# Sh_Outputs_Analog.net
KiCad netlist of a schematic drawn in Altium Designer
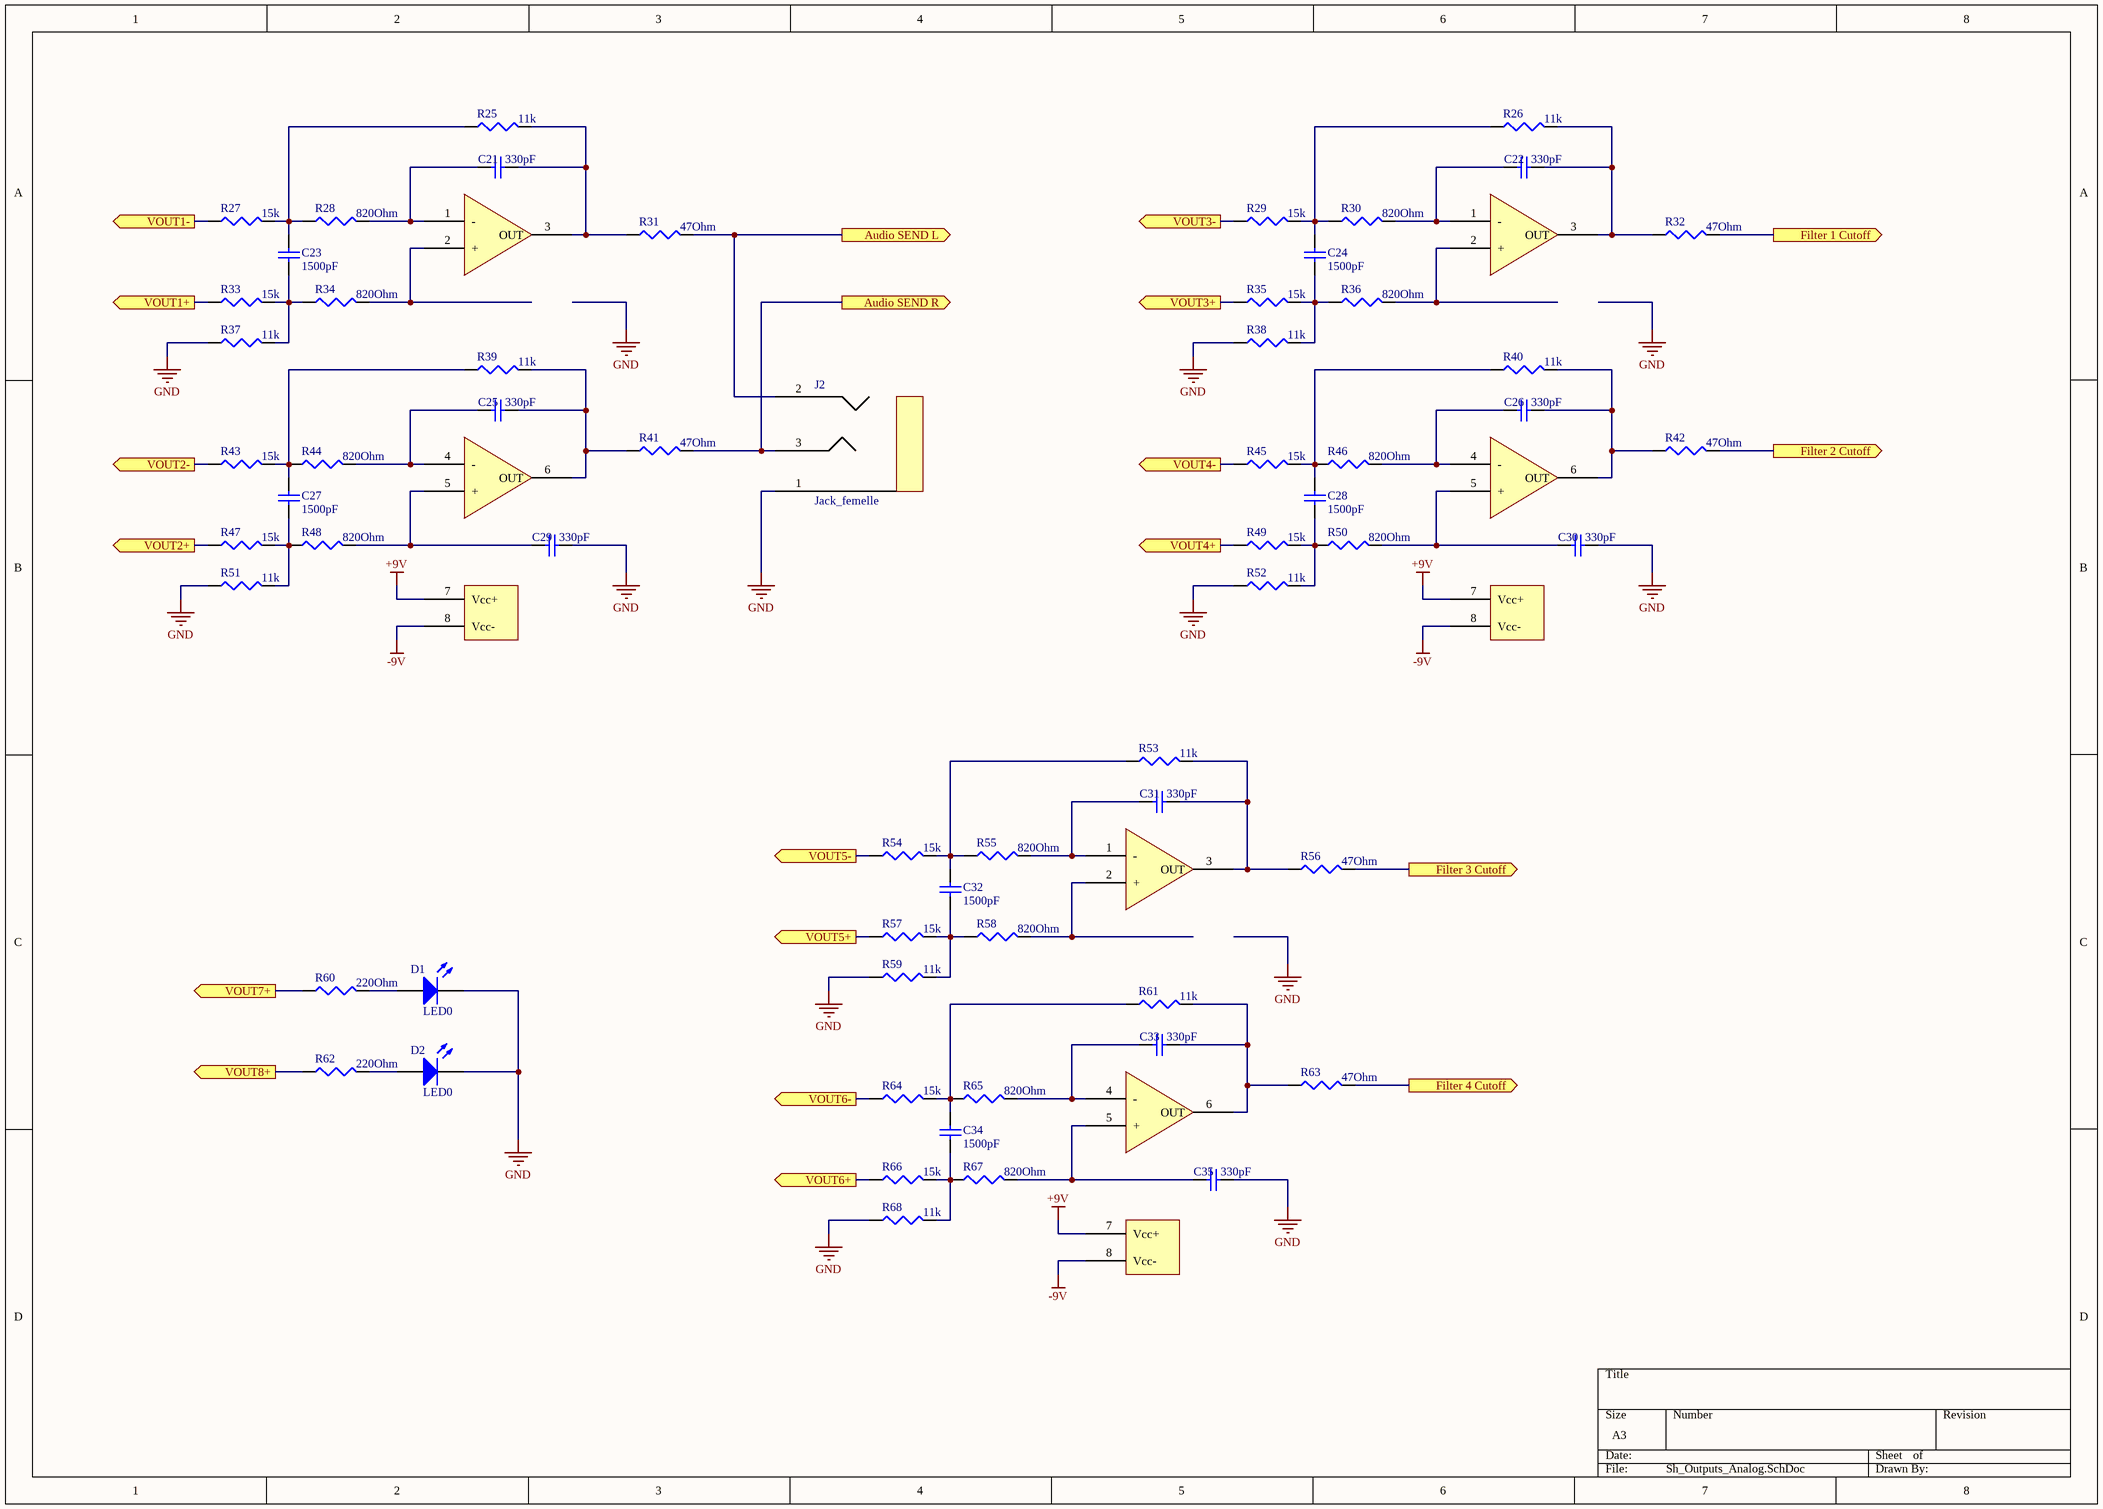
[diagram p0: Sh_Outputs_Analog.SchDoc]

(export (version "E")
  (design (tool "Eeschema 10.0.6"))
  (components
    (comp (ref "C21")
      (value "330pF")
      (footprint "1608[0603]")
      (description "Capacitor (Semiconductor SIM Model)")
      (fields (field (name "Comment") "Cap Semi") (field (name "PUBLISHER") "Altium Limited"))
      (libsource (lib "Miscellaneous Devices") (part "Cap Semi"))
    )
    (comp (ref "C22")
      (value "330pF")
      (footprint "1608[0603]")
      (description "Capacitor (Semiconductor SIM Model)")
      (fields (field (name "Comment") "Cap Semi") (field (name "PUBLISHER") "Altium Limited"))
      (libsource (lib "Miscellaneous Devices") (part "Cap Semi"))
    )
    (comp (ref "C23")
      (value "1500pF")
      (footprint "1608[0603]")
      (description "Capacitor (Semiconductor SIM Model)")
      (fields (field (name "Comment") "Cap Semi") (field (name "PUBLISHER") "Altium Limited"))
      (libsource (lib "Miscellaneous Devices") (part "Cap Semi"))
    )
    (comp (ref "C24")
      (value "1500pF")
      (footprint "1608[0603]")
      (description "Capacitor (Semiconductor SIM Model)")
      (fields (field (name "Comment") "Cap Semi") (field (name "PUBLISHER") "Altium Limited"))
      (libsource (lib "Miscellaneous Devices") (part "Cap Semi"))
    )
    (comp (ref "C25")
      (value "330pF")
      (footprint "1608[0603]")
      (description "Capacitor (Semiconductor SIM Model)")
      (fields (field (name "Comment") "Cap Semi") (field (name "PUBLISHER") "Altium Limited"))
      (libsource (lib "Miscellaneous Devices") (part "Cap Semi"))
    )
    (comp (ref "C26")
      (value "330pF")
      (footprint "1608[0603]")
      (description "Capacitor (Semiconductor SIM Model)")
      (fields (field (name "Comment") "Cap Semi") (field (name "PUBLISHER") "Altium Limited"))
      (libsource (lib "Miscellaneous Devices") (part "Cap Semi"))
    )
    (comp (ref "C27")
      (value "1500pF")
      (footprint "1608[0603]")
      (description "Capacitor (Semiconductor SIM Model)")
      (fields (field (name "Comment") "Cap Semi") (field (name "PUBLISHER") "Altium Limited"))
      (libsource (lib "Miscellaneous Devices") (part "Cap Semi"))
    )
    (comp (ref "C28")
      (value "1500pF")
      (footprint "1608[0603]")
      (description "Capacitor (Semiconductor SIM Model)")
      (fields (field (name "Comment") "Cap Semi") (field (name "PUBLISHER") "Altium Limited"))
      (libsource (lib "Miscellaneous Devices") (part "Cap Semi"))
    )
    (comp (ref "C29")
      (value "330pF")
      (footprint "1608[0603]")
      (description "Capacitor (Semiconductor SIM Model)")
      (fields (field (name "Comment") "Cap Semi") (field (name "PUBLISHER") "Altium Limited"))
      (libsource (lib "Miscellaneous Devices") (part "Cap Semi"))
    )
    (comp (ref "C30")
      (value "330pF")
      (footprint "1608[0603]")
      (description "Capacitor (Semiconductor SIM Model)")
      (fields (field (name "Comment") "Cap Semi") (field (name "PUBLISHER") "Altium Limited"))
      (libsource (lib "Miscellaneous Devices") (part "Cap Semi"))
    )
    (comp (ref "C31")
      (value "330pF")
      (footprint "1608[0603]")
      (description "Capacitor (Semiconductor SIM Model)")
      (fields (field (name "Comment") "Cap Semi") (field (name "PUBLISHER") "Altium Limited"))
      (libsource (lib "Miscellaneous Devices") (part "Cap Semi"))
    )
    (comp (ref "C32")
      (value "1500pF")
      (footprint "1608[0603]")
      (description "Capacitor (Semiconductor SIM Model)")
      (fields (field (name "Comment") "Cap Semi") (field (name "PUBLISHER") "Altium Limited"))
      (libsource (lib "Miscellaneous Devices") (part "Cap Semi"))
    )
    (comp (ref "C33")
      (value "330pF")
      (footprint "1608[0603]")
      (description "Capacitor (Semiconductor SIM Model)")
      (fields (field (name "Comment") "Cap Semi") (field (name "PUBLISHER") "Altium Limited"))
      (libsource (lib "Miscellaneous Devices") (part "Cap Semi"))
    )
    (comp (ref "C34")
      (value "1500pF")
      (footprint "1608[0603]")
      (description "Capacitor (Semiconductor SIM Model)")
      (fields (field (name "Comment") "Cap Semi") (field (name "PUBLISHER") "Altium Limited"))
      (libsource (lib "Miscellaneous Devices") (part "Cap Semi"))
    )
    (comp (ref "C35")
      (value "330pF")
      (footprint "1608[0603]")
      (description "Capacitor (Semiconductor SIM Model)")
      (fields (field (name "Comment") "Cap Semi") (field (name "PUBLISHER") "Altium Limited"))
      (libsource (lib "Miscellaneous Devices") (part "Cap Semi"))
    )
    (comp (ref "D1")
      (value "LED0")
      (footprint "LED-0")
      (description "Typical INFRARED GaAs LED")
      (fields (field (name "PUBLISHER") "Altium Limited"))
      (libsource (lib "Miscellaneous Devices") (part "LED0"))
    )
    (comp (ref "D2")
      (value "LED0")
      (footprint "LED-0")
      (description "Typical INFRARED GaAs LED")
      (fields (field (name "PUBLISHER") "Altium Limited"))
      (libsource (lib "Miscellaneous Devices") (part "LED0"))
    )
    (comp (ref "J2")
      (value "Jack_femelle")
      (footprint "Jack_Femelle")
      (libsource (lib "Bonjour") (part "Jack_femelle"))
    )
    (comp (ref "R25")
      (value "11k")
      (footprint "J1-0603")
      (description "Resistor")
      (fields (field (name "Comment") "Res3") (field (name "PUBLISHER") "Altium Limited"))
      (libsource (lib "Miscellaneous Devices") (part "Res3"))
    )
    (comp (ref "R26")
      (value "11k")
      (footprint "J1-0603")
      (description "Resistor")
      (fields (field (name "Comment") "Res3") (field (name "PUBLISHER") "Altium Limited"))
      (libsource (lib "Miscellaneous Devices") (part "Res3"))
    )
    (comp (ref "R27")
      (value "15k")
      (footprint "J1-0603")
      (description "Resistor")
      (fields (field (name "Comment") "Res3") (field (name "PUBLISHER") "Altium Limited"))
      (libsource (lib "Miscellaneous Devices") (part "Res3"))
    )
    (comp (ref "R28")
      (value "820Ohm")
      (footprint "J1-0603")
      (description "Resistor")
      (fields (field (name "Comment") "Res3") (field (name "PUBLISHER") "Altium Limited"))
      (libsource (lib "Miscellaneous Devices") (part "Res3"))
    )
    (comp (ref "R29")
      (value "15k")
      (footprint "J1-0603")
      (description "Resistor")
      (fields (field (name "Comment") "Res3") (field (name "PUBLISHER") "Altium Limited"))
      (libsource (lib "Miscellaneous Devices") (part "Res3"))
    )
    (comp (ref "R30")
      (value "820Ohm")
      (footprint "J1-0603")
      (description "Resistor")
      (fields (field (name "Comment") "Res3") (field (name "PUBLISHER") "Altium Limited"))
      (libsource (lib "Miscellaneous Devices") (part "Res3"))
    )
    (comp (ref "R31")
      (value "47Ohm")
      (footprint "J1-0603")
      (description "Resistor")
      (fields (field (name "Comment") "Res3") (field (name "PUBLISHER") "Altium Limited"))
      (libsource (lib "Miscellaneous Devices") (part "Res3"))
    )
    (comp (ref "R32")
      (value "47Ohm")
      (footprint "J1-0603")
      (description "Resistor")
      (fields (field (name "Comment") "Res3") (field (name "PUBLISHER") "Altium Limited"))
      (libsource (lib "Miscellaneous Devices") (part "Res3"))
    )
    (comp (ref "R33")
      (value "15k")
      (footprint "J1-0603")
      (description "Resistor")
      (fields (field (name "Comment") "Res3") (field (name "PUBLISHER") "Altium Limited"))
      (libsource (lib "Miscellaneous Devices") (part "Res3"))
    )
    (comp (ref "R34")
      (value "820Ohm")
      (footprint "J1-0603")
      (description "Resistor")
      (fields (field (name "Comment") "Res3") (field (name "PUBLISHER") "Altium Limited"))
      (libsource (lib "Miscellaneous Devices") (part "Res3"))
    )
    (comp (ref "R35")
      (value "15k")
      (footprint "J1-0603")
      (description "Resistor")
      (fields (field (name "Comment") "Res3") (field (name "PUBLISHER") "Altium Limited"))
      (libsource (lib "Miscellaneous Devices") (part "Res3"))
    )
    (comp (ref "R36")
      (value "820Ohm")
      (footprint "J1-0603")
      (description "Resistor")
      (fields (field (name "Comment") "Res3") (field (name "PUBLISHER") "Altium Limited"))
      (libsource (lib "Miscellaneous Devices") (part "Res3"))
    )
    (comp (ref "R37")
      (value "11k")
      (footprint "J1-0603")
      (description "Resistor")
      (fields (field (name "Comment") "Res3") (field (name "PUBLISHER") "Altium Limited"))
      (libsource (lib "Miscellaneous Devices") (part "Res3"))
    )
    (comp (ref "R38")
      (value "11k")
      (footprint "J1-0603")
      (description "Resistor")
      (fields (field (name "Comment") "Res3") (field (name "PUBLISHER") "Altium Limited"))
      (libsource (lib "Miscellaneous Devices") (part "Res3"))
    )
    (comp (ref "R39")
      (value "11k")
      (footprint "J1-0603")
      (description "Resistor")
      (fields (field (name "Comment") "Res3") (field (name "PUBLISHER") "Altium Limited"))
      (libsource (lib "Miscellaneous Devices") (part "Res3"))
    )
    (comp (ref "R40")
      (value "11k")
      (footprint "J1-0603")
      (description "Resistor")
      (fields (field (name "Comment") "Res3") (field (name "PUBLISHER") "Altium Limited"))
      (libsource (lib "Miscellaneous Devices") (part "Res3"))
    )
    (comp (ref "R41")
      (value "47Ohm")
      (footprint "J1-0603")
      (description "Resistor")
      (fields (field (name "Comment") "Res3") (field (name "PUBLISHER") "Altium Limited"))
      (libsource (lib "Miscellaneous Devices") (part "Res3"))
    )
    (comp (ref "R42")
      (value "47Ohm")
      (footprint "J1-0603")
      (description "Resistor")
      (fields (field (name "Comment") "Res3") (field (name "PUBLISHER") "Altium Limited"))
      (libsource (lib "Miscellaneous Devices") (part "Res3"))
    )
    (comp (ref "R43")
      (value "15k")
      (footprint "J1-0603")
      (description "Resistor")
      (fields (field (name "Comment") "Res3") (field (name "PUBLISHER") "Altium Limited"))
      (libsource (lib "Miscellaneous Devices") (part "Res3"))
    )
    (comp (ref "R44")
      (value "820Ohm")
      (footprint "J1-0603")
      (description "Resistor")
      (fields (field (name "Comment") "Res3") (field (name "PUBLISHER") "Altium Limited"))
      (libsource (lib "Miscellaneous Devices") (part "Res3"))
    )
    (comp (ref "R45")
      (value "15k")
      (footprint "J1-0603")
      (description "Resistor")
      (fields (field (name "Comment") "Res3") (field (name "PUBLISHER") "Altium Limited"))
      (libsource (lib "Miscellaneous Devices") (part "Res3"))
    )
    (comp (ref "R46")
      (value "820Ohm")
      (footprint "J1-0603")
      (description "Resistor")
      (fields (field (name "Comment") "Res3") (field (name "PUBLISHER") "Altium Limited"))
      (libsource (lib "Miscellaneous Devices") (part "Res3"))
    )
    (comp (ref "R47")
      (value "15k")
      (footprint "J1-0603")
      (description "Resistor")
      (fields (field (name "Comment") "Res3") (field (name "PUBLISHER") "Altium Limited"))
      (libsource (lib "Miscellaneous Devices") (part "Res3"))
    )
    (comp (ref "R48")
      (value "820Ohm")
      (footprint "J1-0603")
      (description "Resistor")
      (fields (field (name "Comment") "Res3") (field (name "PUBLISHER") "Altium Limited"))
      (libsource (lib "Miscellaneous Devices") (part "Res3"))
    )
    (comp (ref "R49")
      (value "15k")
      (footprint "J1-0603")
      (description "Resistor")
      (fields (field (name "Comment") "Res3") (field (name "PUBLISHER") "Altium Limited"))
      (libsource (lib "Miscellaneous Devices") (part "Res3"))
    )
    (comp (ref "R50")
      (value "820Ohm")
      (footprint "J1-0603")
      (description "Resistor")
      (fields (field (name "Comment") "Res3") (field (name "PUBLISHER") "Altium Limited"))
      (libsource (lib "Miscellaneous Devices") (part "Res3"))
    )
    (comp (ref "R51")
      (value "11k")
      (footprint "J1-0603")
      (description "Resistor")
      (fields (field (name "Comment") "Res3") (field (name "PUBLISHER") "Altium Limited"))
      (libsource (lib "Miscellaneous Devices") (part "Res3"))
    )
    (comp (ref "R52")
      (value "11k")
      (footprint "J1-0603")
      (description "Resistor")
      (fields (field (name "Comment") "Res3") (field (name "PUBLISHER") "Altium Limited"))
      (libsource (lib "Miscellaneous Devices") (part "Res3"))
    )
    (comp (ref "R53")
      (value "11k")
      (footprint "J1-0603")
      (description "Resistor")
      (fields (field (name "Comment") "Res3") (field (name "PUBLISHER") "Altium Limited"))
      (libsource (lib "Miscellaneous Devices") (part "Res3"))
    )
    (comp (ref "R54")
      (value "15k")
      (footprint "J1-0603")
      (description "Resistor")
      (fields (field (name "Comment") "Res3") (field (name "PUBLISHER") "Altium Limited"))
      (libsource (lib "Miscellaneous Devices") (part "Res3"))
    )
    (comp (ref "R55")
      (value "820Ohm")
      (footprint "J1-0603")
      (description "Resistor")
      (fields (field (name "Comment") "Res3") (field (name "PUBLISHER") "Altium Limited"))
      (libsource (lib "Miscellaneous Devices") (part "Res3"))
    )
    (comp (ref "R56")
      (value "47Ohm")
      (footprint "J1-0603")
      (description "Resistor")
      (fields (field (name "Comment") "Res3") (field (name "PUBLISHER") "Altium Limited"))
      (libsource (lib "Miscellaneous Devices") (part "Res3"))
    )
    (comp (ref "R57")
      (value "15k")
      (footprint "J1-0603")
      (description "Resistor")
      (fields (field (name "Comment") "Res3") (field (name "PUBLISHER") "Altium Limited"))
      (libsource (lib "Miscellaneous Devices") (part "Res3"))
    )
    (comp (ref "R58")
      (value "820Ohm")
      (footprint "J1-0603")
      (description "Resistor")
      (fields (field (name "Comment") "Res3") (field (name "PUBLISHER") "Altium Limited"))
      (libsource (lib "Miscellaneous Devices") (part "Res3"))
    )
    (comp (ref "R59")
      (value "11k")
      (footprint "J1-0603")
      (description "Resistor")
      (fields (field (name "Comment") "Res3") (field (name "PUBLISHER") "Altium Limited"))
      (libsource (lib "Miscellaneous Devices") (part "Res3"))
    )
    (comp (ref "R60")
      (value "220Ohm")
      (footprint "J1-0603")
      (description "Resistor")
      (fields (field (name "Comment") "Res3") (field (name "PUBLISHER") "Altium Limited"))
      (libsource (lib "Miscellaneous Devices") (part "Res3"))
    )
    (comp (ref "R61")
      (value "11k")
      (footprint "J1-0603")
      (description "Resistor")
      (fields (field (name "Comment") "Res3") (field (name "PUBLISHER") "Altium Limited"))
      (libsource (lib "Miscellaneous Devices") (part "Res3"))
    )
    (comp (ref "R62")
      (value "220Ohm")
      (footprint "J1-0603")
      (description "Resistor")
      (fields (field (name "Comment") "Res3") (field (name "PUBLISHER") "Altium Limited"))
      (libsource (lib "Miscellaneous Devices") (part "Res3"))
    )
    (comp (ref "R63")
      (value "47Ohm")
      (footprint "J1-0603")
      (description "Resistor")
      (fields (field (name "Comment") "Res3") (field (name "PUBLISHER") "Altium Limited"))
      (libsource (lib "Miscellaneous Devices") (part "Res3"))
    )
    (comp (ref "R64")
      (value "15k")
      (footprint "J1-0603")
      (description "Resistor")
      (fields (field (name "Comment") "Res3") (field (name "PUBLISHER") "Altium Limited"))
      (libsource (lib "Miscellaneous Devices") (part "Res3"))
    )
    (comp (ref "R65")
      (value "820Ohm")
      (footprint "J1-0603")
      (description "Resistor")
      (fields (field (name "Comment") "Res3") (field (name "PUBLISHER") "Altium Limited"))
      (libsource (lib "Miscellaneous Devices") (part "Res3"))
    )
    (comp (ref "R66")
      (value "15k")
      (footprint "J1-0603")
      (description "Resistor")
      (fields (field (name "Comment") "Res3") (field (name "PUBLISHER") "Altium Limited"))
      (libsource (lib "Miscellaneous Devices") (part "Res3"))
    )
    (comp (ref "R67")
      (value "820Ohm")
      (footprint "J1-0603")
      (description "Resistor")
      (fields (field (name "Comment") "Res3") (field (name "PUBLISHER") "Altium Limited"))
      (libsource (lib "Miscellaneous Devices") (part "Res3"))
    )
    (comp (ref "R68")
      (value "11k")
      (footprint "J1-0603")
      (description "Resistor")
      (fields (field (name "Comment") "Res3") (field (name "PUBLISHER") "Altium Limited"))
      (libsource (lib "Miscellaneous Devices") (part "Res3"))
    )
    (comp (ref "U6") (value "Ampli_op") (libsource (lib "Bonjour") (part "Ampli_op")))
    (comp (ref "U7") (value "Ampli_op") (libsource (lib "Bonjour") (part "Ampli_op")))
    (comp (ref "U8") (value "Ampli_op") (libsource (lib "Bonjour") (part "Ampli_op")))
  )
  (nets
    (net (code "1") (name "+9V") (class "Default")
      (node (ref "U6") (pin "7") (pinfunction "Vcc+_7") (pintype "passive"))
      (node (ref "U7") (pin "7") (pinfunction "Vcc+_7") (pintype "passive"))
      (node (ref "U8") (pin "7") (pinfunction "Vcc+_7") (pintype "passive"))
    )
    (net (code "2") (name "-9V") (class "Default")
      (node (ref "U6") (pin "8") (pinfunction "Vcc-_8") (pintype "passive"))
      (node (ref "U7") (pin "8") (pinfunction "Vcc-_8") (pintype "passive"))
      (node (ref "U8") (pin "8") (pinfunction "Vcc-_8") (pintype "passive"))
    )
    (net (code "3") (name "/Audio SEND L") (class "Default")
      (node (ref "J2") (pin "2") (pinfunction "L_2") (pintype "passive"))
      (node (ref "R31") (pin "2") (pinfunction "2_2") (pintype "passive"))
    )
    (net (code "4") (name "/Audio SEND R") (class "Default")
      (node (ref "J2") (pin "3") (pinfunction "R_3") (pintype "passive"))
      (node (ref "R41") (pin "2") (pinfunction "2_2") (pintype "passive"))
    )
    (net (code "5") (name "/Filter 1 Cutoff") (class "Default")
      (node (ref "R32") (pin "2") (pinfunction "2_2") (pintype "passive"))
    )
    (net (code "6") (name "/Filter 2 Cutoff") (class "Default")
      (node (ref "R42") (pin "2") (pinfunction "2_2") (pintype "passive"))
    )
    (net (code "7") (name "/Filter 3 Cutoff") (class "Default")
      (node (ref "R56") (pin "2") (pinfunction "2_2") (pintype "passive"))
    )
    (net (code "8") (name "/Filter 4 Cutoff") (class "Default")
      (node (ref "R63") (pin "2") (pinfunction "2_2") (pintype "passive"))
    )
    (net (code "9") (name "/VOUT1+") (class "Default")
      (node (ref "R33") (pin "1") (pinfunction "1_1") (pintype "passive"))
    )
    (net (code "10") (name "/VOUT1-") (class "Default")
      (node (ref "R27") (pin "1") (pinfunction "1_1") (pintype "passive"))
    )
    (net (code "11") (name "/VOUT2+") (class "Default")
      (node (ref "R47") (pin "1") (pinfunction "1_1") (pintype "passive"))
    )
    (net (code "12") (name "/VOUT2-") (class "Default")
      (node (ref "R43") (pin "1") (pinfunction "1_1") (pintype "passive"))
    )
    (net (code "13") (name "/VOUT3+") (class "Default")
      (node (ref "R35") (pin "1") (pinfunction "1_1") (pintype "passive"))
    )
    (net (code "14") (name "/VOUT3-") (class "Default")
      (node (ref "R29") (pin "1") (pinfunction "1_1") (pintype "passive"))
    )
    (net (code "15") (name "/VOUT4+") (class "Default")
      (node (ref "R49") (pin "1") (pinfunction "1_1") (pintype "passive"))
    )
    (net (code "16") (name "/VOUT4-") (class "Default")
      (node (ref "R45") (pin "1") (pinfunction "1_1") (pintype "passive"))
    )
    (net (code "17") (name "/VOUT5+") (class "Default")
      (node (ref "R57") (pin "1") (pinfunction "1_1") (pintype "passive"))
    )
    (net (code "18") (name "/VOUT5-") (class "Default")
      (node (ref "R54") (pin "1") (pinfunction "1_1") (pintype "passive"))
    )
    (net (code "19") (name "/VOUT6+") (class "Default")
      (node (ref "R66") (pin "1") (pinfunction "1_1") (pintype "passive"))
    )
    (net (code "20") (name "/VOUT6-") (class "Default")
      (node (ref "R64") (pin "1") (pinfunction "1_1") (pintype "passive"))
    )
    (net (code "21") (name "/VOUT7+") (class "Default")
      (node (ref "R60") (pin "1") (pinfunction "1_1") (pintype "passive"))
    )
    (net (code "22") (name "/VOUT8+") (class "Default")
      (node (ref "R62") (pin "1") (pinfunction "1_1") (pintype "passive"))
    )
    (net (code "23") (name "GND") (class "Default")
      (node (ref "C29") (pin "1") (pinfunction "1_1") (pintype "passive"))
      (node (ref "C30") (pin "1") (pinfunction "1_1") (pintype "passive"))
      (node (ref "C35") (pin "1") (pinfunction "1_1") (pintype "passive"))
      (node (ref "D1") (pin "2") (pinfunction "K_2") (pintype "passive"))
      (node (ref "D2") (pin "2") (pinfunction "K_2") (pintype "passive"))
      (node (ref "J2") (pin "1") (pinfunction "GND_1") (pintype "passive"))
      (node (ref "R37") (pin "1") (pinfunction "1_1") (pintype "passive"))
      (node (ref "R38") (pin "1") (pinfunction "1_1") (pintype "passive"))
      (node (ref "R51") (pin "1") (pinfunction "1_1") (pintype "passive"))
      (node (ref "R52") (pin "1") (pinfunction "1_1") (pintype "passive"))
      (node (ref "R59") (pin "1") (pinfunction "1_1") (pintype "passive"))
      (node (ref "R68") (pin "1") (pinfunction "1_1") (pintype "passive"))
    )
    (net (code "24") (name "Net-(C21-Pad1)") (class "Default")
      (node (ref "C21") (pin "1") (pinfunction "1_1") (pintype "passive"))
      (node (ref "R25") (pin "2") (pinfunction "2_2") (pintype "passive"))
      (node (ref "R31") (pin "1") (pinfunction "1_1") (pintype "passive"))
      (node (ref "U6") (pin "3") (pinfunction "OUT_3") (pintype "passive"))
    )
    (net (code "25") (name "Net-(C21-Pad2)") (class "Default")
      (node (ref "C21") (pin "2") (pinfunction "2_2") (pintype "passive"))
      (node (ref "R28") (pin "2") (pinfunction "2_2") (pintype "passive"))
      (node (ref "U6") (pin "1") (pinfunction "-_1") (pintype "passive"))
    )
    (net (code "26") (name "Net-(C22-Pad1)") (class "Default")
      (node (ref "C22") (pin "1") (pinfunction "1_1") (pintype "passive"))
      (node (ref "R26") (pin "2") (pinfunction "2_2") (pintype "passive"))
      (node (ref "R32") (pin "1") (pinfunction "1_1") (pintype "passive"))
      (node (ref "U7") (pin "3") (pinfunction "OUT_3") (pintype "passive"))
    )
    (net (code "27") (name "Net-(C22-Pad2)") (class "Default")
      (node (ref "C22") (pin "2") (pinfunction "2_2") (pintype "passive"))
      (node (ref "R30") (pin "2") (pinfunction "2_2") (pintype "passive"))
      (node (ref "U7") (pin "1") (pinfunction "-_1") (pintype "passive"))
    )
    (net (code "28") (name "Net-(C23-Pad1)") (class "Default")
      (node (ref "C23") (pin "1") (pinfunction "1_1") (pintype "passive"))
      (node (ref "R33") (pin "2") (pinfunction "2_2") (pintype "passive"))
      (node (ref "R34") (pin "1") (pinfunction "1_1") (pintype "passive"))
      (node (ref "R37") (pin "2") (pinfunction "2_2") (pintype "passive"))
    )
    (net (code "29") (name "Net-(C23-Pad2)") (class "Default")
      (node (ref "C23") (pin "2") (pinfunction "2_2") (pintype "passive"))
      (node (ref "R25") (pin "1") (pinfunction "1_1") (pintype "passive"))
      (node (ref "R27") (pin "2") (pinfunction "2_2") (pintype "passive"))
      (node (ref "R28") (pin "1") (pinfunction "1_1") (pintype "passive"))
    )
    (net (code "30") (name "Net-(C24-Pad1)") (class "Default")
      (node (ref "C24") (pin "1") (pinfunction "1_1") (pintype "passive"))
      (node (ref "R35") (pin "2") (pinfunction "2_2") (pintype "passive"))
      (node (ref "R36") (pin "1") (pinfunction "1_1") (pintype "passive"))
      (node (ref "R38") (pin "2") (pinfunction "2_2") (pintype "passive"))
    )
    (net (code "31") (name "Net-(C24-Pad2)") (class "Default")
      (node (ref "C24") (pin "2") (pinfunction "2_2") (pintype "passive"))
      (node (ref "R26") (pin "1") (pinfunction "1_1") (pintype "passive"))
      (node (ref "R29") (pin "2") (pinfunction "2_2") (pintype "passive"))
      (node (ref "R30") (pin "1") (pinfunction "1_1") (pintype "passive"))
    )
    (net (code "32") (name "Net-(C25-Pad1)") (class "Default")
      (node (ref "C25") (pin "1") (pinfunction "1_1") (pintype "passive"))
      (node (ref "R39") (pin "2") (pinfunction "2_2") (pintype "passive"))
      (node (ref "R41") (pin "1") (pinfunction "1_1") (pintype "passive"))
      (node (ref "U6") (pin "6") (pinfunction "OUT_6") (pintype "passive"))
    )
    (net (code "33") (name "Net-(C25-Pad2)") (class "Default")
      (node (ref "C25") (pin "2") (pinfunction "2_2") (pintype "passive"))
      (node (ref "R44") (pin "2") (pinfunction "2_2") (pintype "passive"))
      (node (ref "U6") (pin "4") (pinfunction "-_4") (pintype "passive"))
    )
    (net (code "34") (name "Net-(C26-Pad1)") (class "Default")
      (node (ref "C26") (pin "1") (pinfunction "1_1") (pintype "passive"))
      (node (ref "R40") (pin "2") (pinfunction "2_2") (pintype "passive"))
      (node (ref "R42") (pin "1") (pinfunction "1_1") (pintype "passive"))
      (node (ref "U7") (pin "6") (pinfunction "OUT_6") (pintype "passive"))
    )
    (net (code "35") (name "Net-(C26-Pad2)") (class "Default")
      (node (ref "C26") (pin "2") (pinfunction "2_2") (pintype "passive"))
      (node (ref "R46") (pin "2") (pinfunction "2_2") (pintype "passive"))
      (node (ref "U7") (pin "4") (pinfunction "-_4") (pintype "passive"))
    )
    (net (code "36") (name "Net-(C27-Pad1)") (class "Default")
      (node (ref "C27") (pin "1") (pinfunction "1_1") (pintype "passive"))
      (node (ref "R47") (pin "2") (pinfunction "2_2") (pintype "passive"))
      (node (ref "R48") (pin "1") (pinfunction "1_1") (pintype "passive"))
      (node (ref "R51") (pin "2") (pinfunction "2_2") (pintype "passive"))
    )
    (net (code "37") (name "Net-(C27-Pad2)") (class "Default")
      (node (ref "C27") (pin "2") (pinfunction "2_2") (pintype "passive"))
      (node (ref "R39") (pin "1") (pinfunction "1_1") (pintype "passive"))
      (node (ref "R43") (pin "2") (pinfunction "2_2") (pintype "passive"))
      (node (ref "R44") (pin "1") (pinfunction "1_1") (pintype "passive"))
    )
    (net (code "38") (name "Net-(C28-Pad1)") (class "Default")
      (node (ref "C28") (pin "1") (pinfunction "1_1") (pintype "passive"))
      (node (ref "R49") (pin "2") (pinfunction "2_2") (pintype "passive"))
      (node (ref "R50") (pin "1") (pinfunction "1_1") (pintype "passive"))
      (node (ref "R52") (pin "2") (pinfunction "2_2") (pintype "passive"))
    )
    (net (code "39") (name "Net-(C28-Pad2)") (class "Default")
      (node (ref "C28") (pin "2") (pinfunction "2_2") (pintype "passive"))
      (node (ref "R40") (pin "1") (pinfunction "1_1") (pintype "passive"))
      (node (ref "R45") (pin "2") (pinfunction "2_2") (pintype "passive"))
      (node (ref "R46") (pin "1") (pinfunction "1_1") (pintype "passive"))
    )
    (net (code "40") (name "Net-(C29-Pad2)") (class "Default")
      (node (ref "C29") (pin "2") (pinfunction "2_2") (pintype "passive"))
      (node (ref "R48") (pin "2") (pinfunction "2_2") (pintype "passive"))
      (node (ref "U6") (pin "5") (pinfunction "+_5") (pintype "passive"))
    )
    (net (code "41") (name "Net-(C30-Pad2)") (class "Default")
      (node (ref "C30") (pin "2") (pinfunction "2_2") (pintype "passive"))
      (node (ref "R50") (pin "2") (pinfunction "2_2") (pintype "passive"))
      (node (ref "U7") (pin "5") (pinfunction "+_5") (pintype "passive"))
    )
    (net (code "42") (name "Net-(C31-Pad1)") (class "Default")
      (node (ref "C31") (pin "1") (pinfunction "1_1") (pintype "passive"))
      (node (ref "R53") (pin "2") (pinfunction "2_2") (pintype "passive"))
      (node (ref "R56") (pin "1") (pinfunction "1_1") (pintype "passive"))
      (node (ref "U8") (pin "3") (pinfunction "OUT_3") (pintype "passive"))
    )
    (net (code "43") (name "Net-(C31-Pad2)") (class "Default")
      (node (ref "C31") (pin "2") (pinfunction "2_2") (pintype "passive"))
      (node (ref "R55") (pin "2") (pinfunction "2_2") (pintype "passive"))
      (node (ref "U8") (pin "1") (pinfunction "-_1") (pintype "passive"))
    )
    (net (code "44") (name "Net-(C32-Pad1)") (class "Default")
      (node (ref "C32") (pin "1") (pinfunction "1_1") (pintype "passive"))
      (node (ref "R57") (pin "2") (pinfunction "2_2") (pintype "passive"))
      (node (ref "R58") (pin "1") (pinfunction "1_1") (pintype "passive"))
      (node (ref "R59") (pin "2") (pinfunction "2_2") (pintype "passive"))
    )
    (net (code "45") (name "Net-(C32-Pad2)") (class "Default")
      (node (ref "C32") (pin "2") (pinfunction "2_2") (pintype "passive"))
      (node (ref "R53") (pin "1") (pinfunction "1_1") (pintype "passive"))
      (node (ref "R54") (pin "2") (pinfunction "2_2") (pintype "passive"))
      (node (ref "R55") (pin "1") (pinfunction "1_1") (pintype "passive"))
    )
    (net (code "46") (name "Net-(C33-Pad1)") (class "Default")
      (node (ref "C33") (pin "1") (pinfunction "1_1") (pintype "passive"))
      (node (ref "R61") (pin "2") (pinfunction "2_2") (pintype "passive"))
      (node (ref "R63") (pin "1") (pinfunction "1_1") (pintype "passive"))
      (node (ref "U8") (pin "6") (pinfunction "OUT_6") (pintype "passive"))
    )
    (net (code "47") (name "Net-(C33-Pad2)") (class "Default")
      (node (ref "C33") (pin "2") (pinfunction "2_2") (pintype "passive"))
      (node (ref "R65") (pin "2") (pinfunction "2_2") (pintype "passive"))
      (node (ref "U8") (pin "4") (pinfunction "-_4") (pintype "passive"))
    )
    (net (code "48") (name "Net-(C34-Pad1)") (class "Default")
      (node (ref "C34") (pin "1") (pinfunction "1_1") (pintype "passive"))
      (node (ref "R66") (pin "2") (pinfunction "2_2") (pintype "passive"))
      (node (ref "R67") (pin "1") (pinfunction "1_1") (pintype "passive"))
      (node (ref "R68") (pin "2") (pinfunction "2_2") (pintype "passive"))
    )
    (net (code "49") (name "Net-(C34-Pad2)") (class "Default")
      (node (ref "C34") (pin "2") (pinfunction "2_2") (pintype "passive"))
      (node (ref "R61") (pin "1") (pinfunction "1_1") (pintype "passive"))
      (node (ref "R64") (pin "2") (pinfunction "2_2") (pintype "passive"))
      (node (ref "R65") (pin "1") (pinfunction "1_1") (pintype "passive"))
    )
    (net (code "50") (name "Net-(C35-Pad2)") (class "Default")
      (node (ref "C35") (pin "2") (pinfunction "2_2") (pintype "passive"))
      (node (ref "R67") (pin "2") (pinfunction "2_2") (pintype "passive"))
      (node (ref "U8") (pin "5") (pinfunction "+_5") (pintype "passive"))
    )
    (net (code "51") (name "Net-(D1-A)") (class "Default")
      (node (ref "D1") (pin "1") (pinfunction "A_1") (pintype "passive"))
      (node (ref "R60") (pin "2") (pinfunction "2_2") (pintype "passive"))
    )
    (net (code "52") (name "Net-(D2-A)") (class "Default")
      (node (ref "D2") (pin "1") (pinfunction "A_1") (pintype "passive"))
      (node (ref "R62") (pin "2") (pinfunction "2_2") (pintype "passive"))
    )
    (net (code "53") (name "Net-(R34-Pad2)") (class "Default")
      (node (ref "R34") (pin "2") (pinfunction "2_2") (pintype "passive"))
      (node (ref "U6") (pin "2") (pinfunction "+_2") (pintype "passive"))
    )
    (net (code "54") (name "Net-(R36-Pad2)") (class "Default")
      (node (ref "R36") (pin "2") (pinfunction "2_2") (pintype "passive"))
      (node (ref "U7") (pin "2") (pinfunction "+_2") (pintype "passive"))
    )
    (net (code "55") (name "Net-(R58-Pad2)") (class "Default")
      (node (ref "R58") (pin "2") (pinfunction "2_2") (pintype "passive"))
      (node (ref "U8") (pin "2") (pinfunction "+_2") (pintype "passive"))
    )
  )
)
